# InverterSchematic.net
KiCad netlist of a schematic drawn in Altium Designer
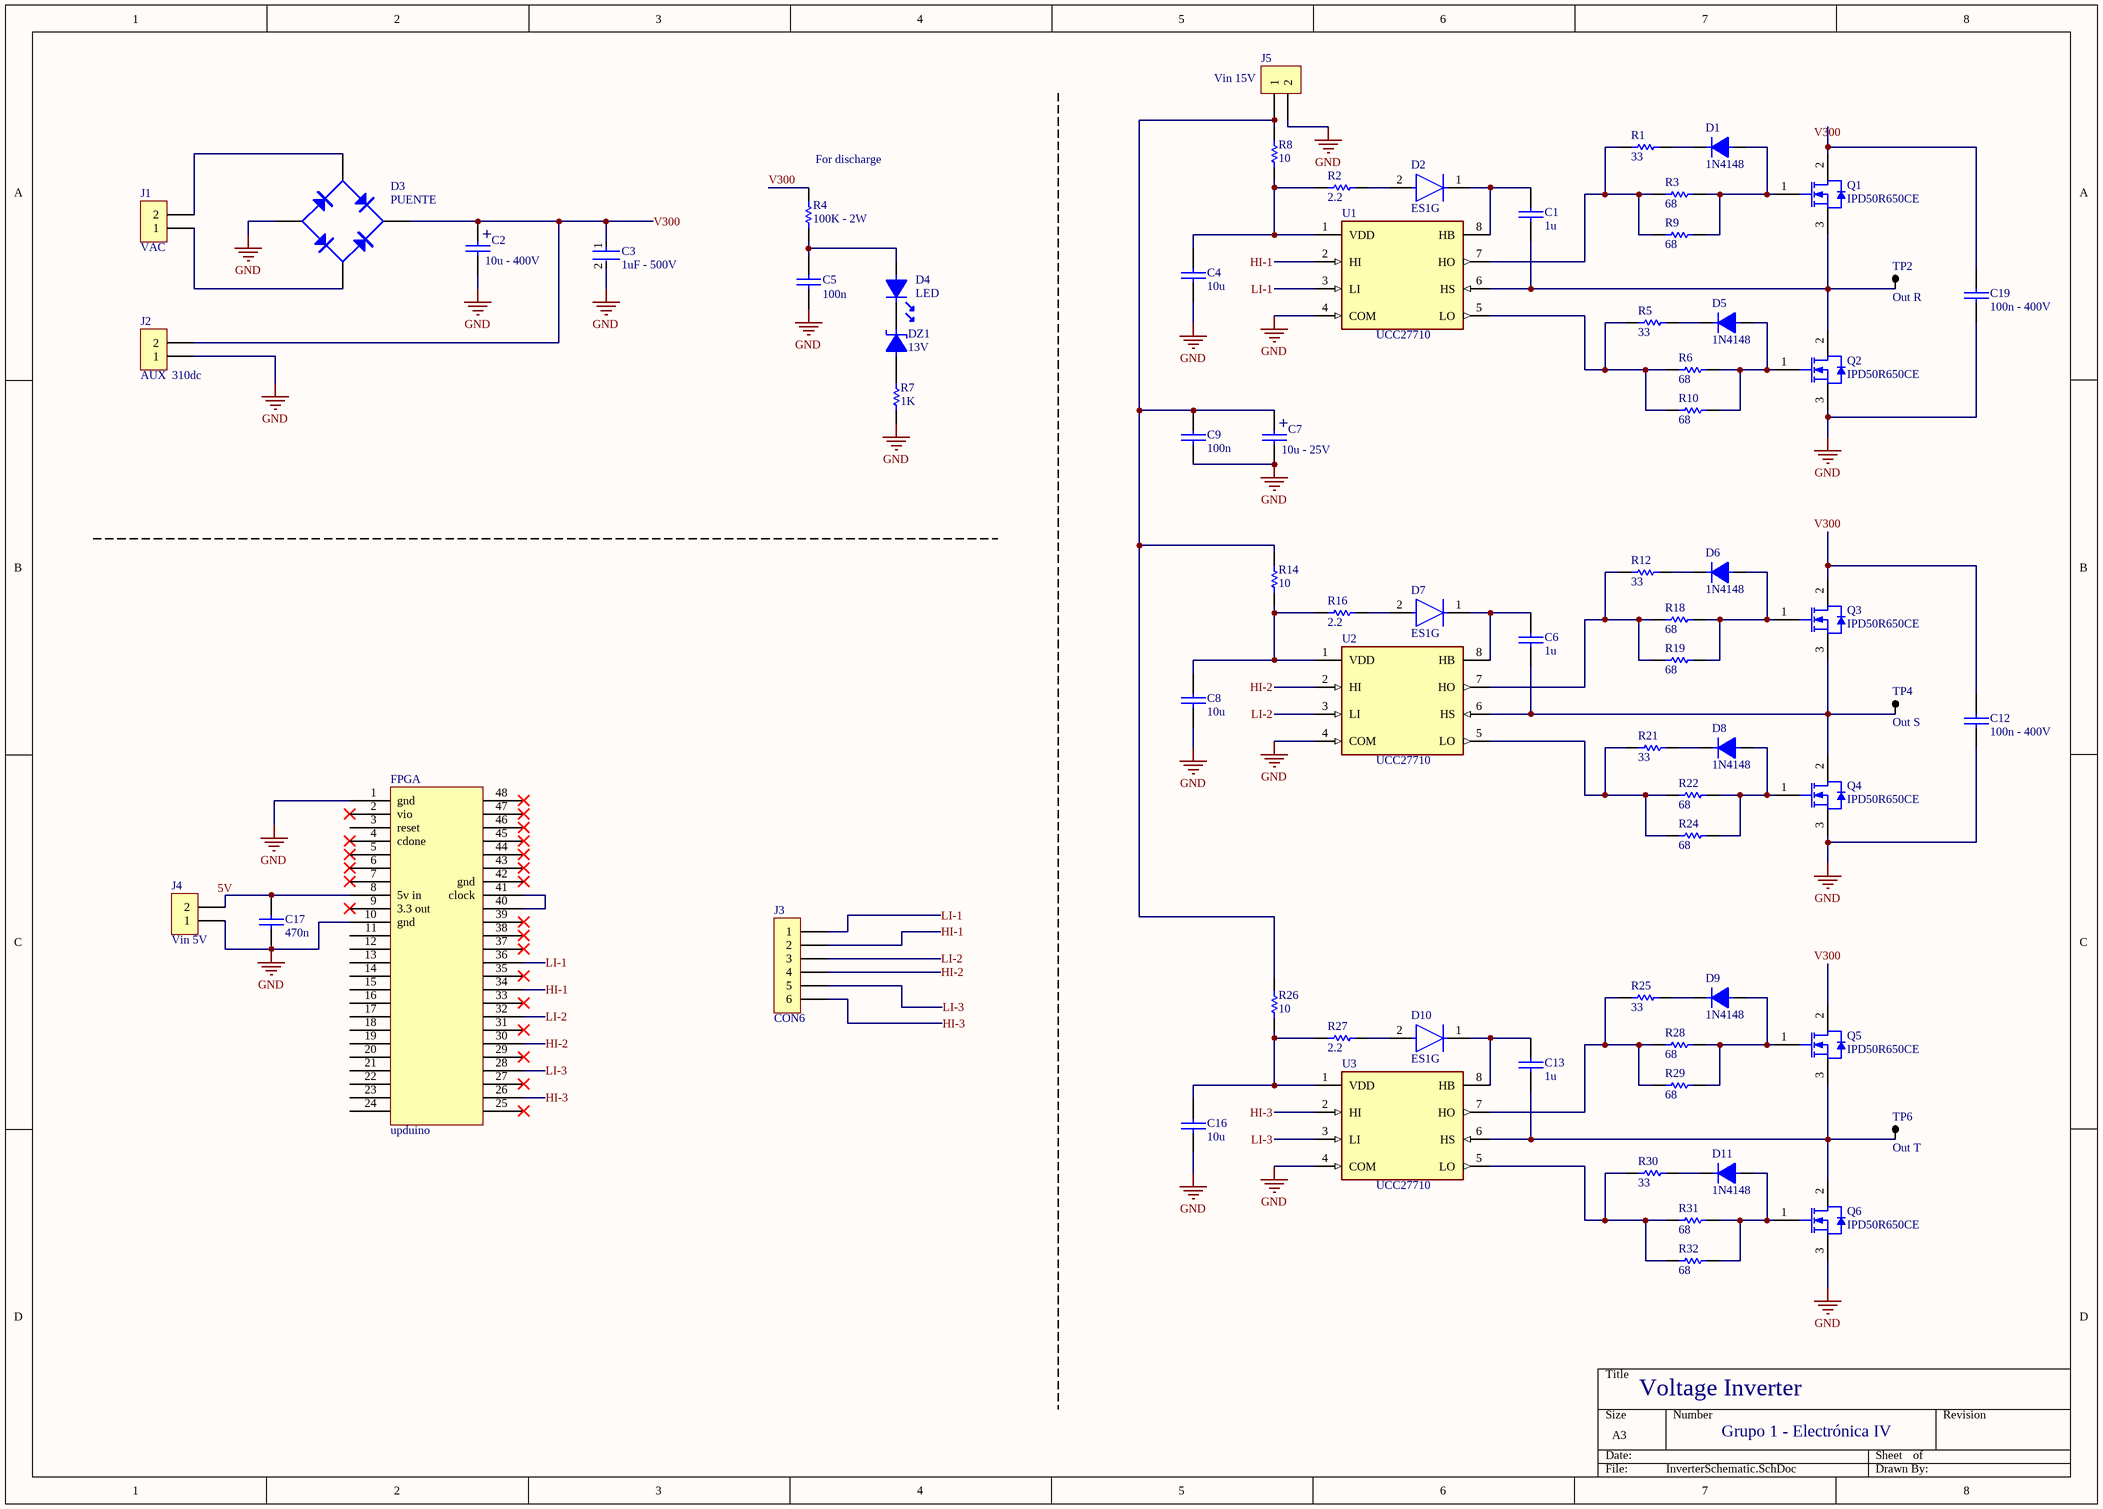
[diagram p0: InverterSchematic.SchDoc]

(export (version "E")
  (design (tool "Eeschema 10.0.6"))
  (components
    (comp (ref "C1") (value "1u") (footprint "0805") (libsource (lib "LIBEBAL") (part "CAP")))
    (comp (ref "C2")
      (value "10u - 400V")
      (footprint "CAP200RP2")
      (libsource (lib "LIBEBAL Tobi") (part "CAPPOL"))
    )
    (comp (ref "C3")
      (value "1uF - 500V")
      (footprint "FP-GRM55D-0_4-IPC_B")
      (description "Chip Multilayer Ceramic Capacitors for General Purpose, 2220, 1.0uF, X7R, 15%, 10%, 500V")
      (fields (field (name "VOLTAGE") "250V") (field (name "TOLERANCE") "10%"))
      (libsource (lib "Altium Content Vault") (part "b4654b650e69147ec39a6b967a45e02"))
    )
    (comp (ref "C4") (value "10u") (footprint "0805") (libsource (lib "LIBEBAL") (part "CAP")))
    (comp (ref "C5") (value "100n") (footprint "0805") (libsource (lib "LIBEBAL Tobi") (part "CAP")))
    (comp (ref "C6") (value "1u") (footprint "0805") (libsource (lib "LIBEBAL") (part "CAP")))
    (comp (ref "C7")
      (value "10u - 25V")
      (footprint "CAP100RP")
      (libsource (lib "LIBEBAL Tobi") (part "CAPPOL"))
    )
    (comp (ref "C8") (value "10u") (footprint "0805") (libsource (lib "LIBEBAL") (part "CAP")))
    (comp (ref "C9") (value "100n") (footprint "CAP200") (libsource (lib "LIBEBAL") (part "CAP")))
    (comp (ref "C12") (value "100n - 400V") (footprint "CAP200") (libsource (lib "LIBEBAL") (part "CAP")))
    (comp (ref "C13") (value "1u") (footprint "0805") (libsource (lib "LIBEBAL") (part "CAP")))
    (comp (ref "C16") (value "10u") (footprint "0805") (libsource (lib "LIBEBAL") (part "CAP")))
    (comp (ref "C17") (value "470n") (footprint "0805") (libsource (lib "LIBEBAL") (part "CAP")))
    (comp (ref "C19") (value "100n - 400V") (footprint "CAP200") (libsource (lib "LIBEBAL") (part "CAP")))
    (comp (ref "D1") (value "1N4148") (footprint "DO41") (libsource (lib "LIBEBAL") (part "DIODO")))
    (comp (ref "D2")
      (value "ES1G")
      (footprint "FP-403AE-MFG")
      (description "DIODE GEN PURP 400V 1A SMA")
      (fields
        (field (name "OCTOPART") "https://octopart.com/es1g-on+semiconductor-84324858")
        (field (name "MANUFACTURER") "ON Semiconductor")
      )
      (libsource (lib "Altium Content Vault") (part "d7152d700b627762746794eb795d46e"))
    )
    (comp (ref "D3")
      (value "PUENTE")
      (footprint "PUENTE - W10M")
      (libsource (lib "LIBEBAL Tobi") (part "PUENTE"))
    )
    (comp (ref "D4") (value "LED") (footprint "LED3") (libsource (lib "LIBEBAL Tobi") (part "LED")))
    (comp (ref "D5") (value "1N4148") (footprint "DO41") (libsource (lib "LIBEBAL") (part "DIODO")))
    (comp (ref "D6") (value "1N4148") (footprint "DO41") (libsource (lib "LIBEBAL") (part "DIODO")))
    (comp (ref "D7")
      (value "ES1G")
      (footprint "FP-403AE-MFG")
      (description "DIODE GEN PURP 400V 1A SMA")
      (fields
        (field (name "OCTOPART") "https://octopart.com/es1g-on+semiconductor-84324858")
        (field (name "MANUFACTURER") "ON Semiconductor")
      )
      (libsource (lib "Altium Content Vault") (part "d7152d700b627762746794eb795d46e"))
    )
    (comp (ref "D8") (value "1N4148") (footprint "DO41") (libsource (lib "LIBEBAL") (part "DIODO")))
    (comp (ref "D9") (value "1N4148") (footprint "DO41") (libsource (lib "LIBEBAL") (part "DIODO")))
    (comp (ref "D10")
      (value "ES1G")
      (footprint "FP-403AE-MFG")
      (description "DIODE GEN PURP 400V 1A SMA")
      (fields
        (field (name "OCTOPART") "https://octopart.com/es1g-on+semiconductor-84324858")
        (field (name "MANUFACTURER") "ON Semiconductor")
      )
      (libsource (lib "Altium Content Vault") (part "d7152d700b627762746794eb795d46e"))
    )
    (comp (ref "D11") (value "1N4148") (footprint "DO41") (libsource (lib "LIBEBAL") (part "DIODO")))
    (comp (ref "DZ1") (value "13V") (footprint "DO41") (libsource (lib "LIBEBAL Tobi") (part "DIODO ZENER")))
    (comp (ref "FPGA")
      (value "upduino")
      (footprint "FPGA")
      (description "upduino v3.0")
      (libsource (lib "InverterSchLib") (part "FPGA"))
    )
    (comp (ref "J1") (value "VAC") (footprint "BORNERA2") (libsource (lib "LIBEBAL Tobi") (part "BORNERA 2")))
    (comp (ref "J2")
      (value "AUX  310dc")
      (footprint "BORNERA2")
      (libsource (lib "LIBEBAL Tobi") (part "BORNERA 2"))
    )
    (comp (ref "J3") (value "CON6") (footprint "SIP6") (libsource (lib "LIBEBAL") (part "CON6")))
    (comp (ref "J4")
      (value "Vin 5V")
      (footprint "SIP2")
      (description "UPDuino Power Input")
      (libsource (lib "LIBEBAL Tobi") (part "CON2"))
    )
    (comp (ref "J5")
      (value "Vin 15V")
      (footprint "SIP2")
      (description "UPDuino Power Input")
      (libsource (lib "") (part "CON2_1"))
    )
    (comp (ref "Q1")
      (value "IPD50R650CE")
      (footprint "INF-PG-TO252-3-313_N")
      (fields (field (name "MANUFACTURER") "Infineon"))
      (libsource (lib "Altium Content Vault") (part "INF-NEMOS-GDS-3"))
    )
    (comp (ref "Q2")
      (value "IPD50R650CE")
      (footprint "INF-PG-TO252-3-313_N")
      (fields (field (name "MANUFACTURER") "Infineon"))
      (libsource (lib "Altium Content Vault") (part "INF-NEMOS-GDS-3"))
    )
    (comp (ref "Q3")
      (value "IPD50R650CE")
      (footprint "INF-PG-TO252-3-313_N")
      (fields (field (name "MANUFACTURER") "Infineon"))
      (libsource (lib "Altium Content Vault") (part "INF-NEMOS-GDS-3"))
    )
    (comp (ref "Q4")
      (value "IPD50R650CE")
      (footprint "INF-PG-TO252-3-313_N")
      (fields (field (name "MANUFACTURER") "Infineon"))
      (libsource (lib "Altium Content Vault") (part "INF-NEMOS-GDS-3"))
    )
    (comp (ref "Q5")
      (value "IPD50R650CE")
      (footprint "INF-PG-TO252-3-313_N")
      (fields (field (name "MANUFACTURER") "Infineon"))
      (libsource (lib "Altium Content Vault") (part "INF-NEMOS-GDS-3"))
    )
    (comp (ref "Q6")
      (value "IPD50R650CE")
      (footprint "INF-PG-TO252-3-313_N")
      (fields (field (name "MANUFACTURER") "Infineon"))
      (libsource (lib "Altium Content Vault") (part "INF-NEMOS-GDS-3"))
    )
    (comp (ref "R1")
      (value "33")
      (footprint "0805")
      (description "33?")
      (libsource (lib "LIBEBAL") (part "RES"))
    )
    (comp (ref "R2") (value "2.2") (footprint "RES300") (libsource (lib "LIBEBAL") (part "RES")))
    (comp (ref "R3") (value "68") (footprint "0805") (libsource (lib "LIBEBAL") (part "RES")))
    (comp (ref "R4") (value "100K - 2W") (footprint "RES300") (libsource (lib "LIBEBAL Tobi") (part "RES")))
    (comp (ref "R5") (value "33") (footprint "0805") (libsource (lib "LIBEBAL") (part "RES")))
    (comp (ref "R6") (value "68") (footprint "0805") (libsource (lib "LIBEBAL") (part "RES")))
    (comp (ref "R7") (value "1K") (footprint "0805") (libsource (lib "LIBEBAL") (part "RES")))
    (comp (ref "R8") (value "10") (footprint "RES300") (libsource (lib "LIBEBAL") (part "RES")))
    (comp (ref "R9") (value "68") (footprint "0805") (libsource (lib "LIBEBAL") (part "RES")))
    (comp (ref "R10") (value "68") (footprint "0805") (libsource (lib "LIBEBAL") (part "RES")))
    (comp (ref "R12")
      (value "33")
      (footprint "0805")
      (description "33?")
      (libsource (lib "LIBEBAL") (part "RES"))
    )
    (comp (ref "R14") (value "10") (footprint "RES300") (libsource (lib "LIBEBAL") (part "RES")))
    (comp (ref "R16") (value "2.2") (footprint "RES300") (libsource (lib "LIBEBAL") (part "RES")))
    (comp (ref "R18") (value "68") (footprint "0805") (libsource (lib "LIBEBAL") (part "RES")))
    (comp (ref "R19") (value "68") (footprint "0805") (libsource (lib "LIBEBAL") (part "RES")))
    (comp (ref "R21") (value "33") (footprint "0805") (libsource (lib "LIBEBAL") (part "RES")))
    (comp (ref "R22") (value "68") (footprint "0805") (libsource (lib "LIBEBAL") (part "RES")))
    (comp (ref "R24") (value "68") (footprint "0805") (libsource (lib "LIBEBAL") (part "RES")))
    (comp (ref "R25")
      (value "33")
      (footprint "0805")
      (description "33?")
      (libsource (lib "LIBEBAL") (part "RES"))
    )
    (comp (ref "R26") (value "10") (footprint "RES300") (libsource (lib "LIBEBAL") (part "RES")))
    (comp (ref "R27") (value "2.2") (footprint "RES300") (libsource (lib "LIBEBAL") (part "RES")))
    (comp (ref "R28") (value "68") (footprint "0805") (libsource (lib "LIBEBAL") (part "RES")))
    (comp (ref "R29") (value "68") (footprint "0805") (libsource (lib "LIBEBAL") (part "RES")))
    (comp (ref "R30") (value "33") (footprint "0805") (libsource (lib "LIBEBAL") (part "RES")))
    (comp (ref "R31") (value "68") (footprint "0805") (libsource (lib "LIBEBAL") (part "RES")))
    (comp (ref "R32") (value "68") (footprint "0805") (libsource (lib "LIBEBAL") (part "RES")))
    (comp (ref "TP2") (value "Out R") (footprint "TPTH") (libsource (lib "LIBEBAL") (part "TP")))
    (comp (ref "TP4") (value "Out S") (footprint "TPTH") (libsource (lib "LIBEBAL") (part "TP")))
    (comp (ref "TP6") (value "Out T") (footprint "TPTH") (libsource (lib "LIBEBAL") (part "TP")))
    (comp (ref "U1")
      (value "UCC27710")
      (footprint "FP-PG-DSO-8-IPC_C")
      (description "GATE DRVR HI/LOW SIDE 8SOIC")
      (libsource (lib "Altium Content Vault") (part "f43bf47bf2763d79e2fe7860ecc000c"))
    )
    (comp (ref "U2")
      (value "UCC27710")
      (footprint "FP-PG-DSO-8-IPC_C")
      (description "GATE DRVR HI/LOW SIDE 8SOIC")
      (libsource (lib "Altium Content Vault") (part "f43bf47bf2763d79e2fe7860ecc000c"))
    )
    (comp (ref "U3")
      (value "UCC27710")
      (footprint "FP-PG-DSO-8-IPC_C")
      (description "GATE DRVR HI/LOW SIDE 8SOIC")
      (libsource (lib "Altium Content Vault") (part "f43bf47bf2763d79e2fe7860ecc000c"))
    )
  )
  (nets
    (net (code "1") (name "/5V") (class "Default")
      (node (ref "C17") (pin "1") (pinfunction "1_1") (pintype "passive"))
      (node (ref "FPGA") (pin "8") (pinfunction "5v_in_8") (pintype "passive"))
      (node (ref "J4") (pin "2") (pinfunction "2_2") (pintype "passive"))
    )
    (net (code "2") (name "/HI-1") (class "Default")
      (node (ref "FPGA") (pin "34") (pintype "passive"))
      (node (ref "J3") (pin "2") (pinfunction "2_2") (pintype "passive"))
      (node (ref "U1") (pin "2") (pinfunction "HI_2") (pintype "input"))
    )
    (net (code "3") (name "/HI-2") (class "Default")
      (node (ref "FPGA") (pin "30") (pintype "passive"))
      (node (ref "J3") (pin "4") (pinfunction "4_4") (pintype "passive"))
      (node (ref "U2") (pin "2") (pinfunction "HI_2") (pintype "input"))
    )
    (net (code "4") (name "/HI-3") (class "Default")
      (node (ref "FPGA") (pin "26") (pintype "passive"))
      (node (ref "J3") (pin "6") (pinfunction "6_6") (pintype "passive"))
      (node (ref "U3") (pin "2") (pinfunction "HI_2") (pintype "input"))
    )
    (net (code "5") (name "/LI-1") (class "Default")
      (node (ref "FPGA") (pin "36") (pintype "passive"))
      (node (ref "J3") (pin "1") (pinfunction "1_1") (pintype "passive"))
      (node (ref "U1") (pin "3") (pinfunction "LI_3") (pintype "input"))
    )
    (net (code "6") (name "/LI-2") (class "Default")
      (node (ref "FPGA") (pin "32") (pintype "passive"))
      (node (ref "J3") (pin "3") (pinfunction "3_3") (pintype "passive"))
      (node (ref "U2") (pin "3") (pinfunction "LI_3") (pintype "input"))
    )
    (net (code "7") (name "/LI-3") (class "Default")
      (node (ref "FPGA") (pin "28") (pintype "passive"))
      (node (ref "J3") (pin "5") (pinfunction "5_5") (pintype "passive"))
      (node (ref "U3") (pin "3") (pinfunction "LI_3") (pintype "input"))
    )
    (net (code "8") (name "/V300") (class "Default")
      (node (ref "C12") (pin "1") (pinfunction "1_1") (pintype "passive"))
      (node (ref "C19") (pin "1") (pinfunction "1_1") (pintype "passive"))
      (node (ref "C2") (pin "1") (pinfunction "1_1") (pintype "passive"))
      (node (ref "C3") (pin "1") (pinfunction "1_1") (pintype "passive"))
      (node (ref "D3") (pin "1") (pinfunction "V+_1") (pintype "passive"))
      (node (ref "J2") (pin "2") (pinfunction "2_2") (pintype "passive"))
      (node (ref "Q1") (pin "2") (pinfunction "DRAIN_2") (pintype "passive"))
      (node (ref "Q3") (pin "2") (pinfunction "DRAIN_2") (pintype "passive"))
      (node (ref "Q5") (pin "2") (pinfunction "DRAIN_2") (pintype "passive"))
      (node (ref "R4") (pin "2") (pinfunction "2_2") (pintype "passive"))
    )
    (net (code "9") (name "GND") (class "Default")
      (node (ref "C12") (pin "2") (pinfunction "2_2") (pintype "passive"))
      (node (ref "C16") (pin "2") (pinfunction "2_2") (pintype "passive"))
      (node (ref "C17") (pin "2") (pinfunction "2_2") (pintype "passive"))
      (node (ref "C19") (pin "2") (pinfunction "2_2") (pintype "passive"))
      (node (ref "C2") (pin "2") (pinfunction "2_2") (pintype "passive"))
      (node (ref "C3") (pin "2") (pinfunction "2_2") (pintype "passive"))
      (node (ref "C4") (pin "2") (pinfunction "2_2") (pintype "passive"))
      (node (ref "C5") (pin "1") (pinfunction "1_1") (pintype "passive"))
      (node (ref "C7") (pin "2") (pinfunction "2_2") (pintype "passive"))
      (node (ref "C8") (pin "2") (pinfunction "2_2") (pintype "passive"))
      (node (ref "C9") (pin "2") (pinfunction "2_2") (pintype "passive"))
      (node (ref "D3") (pin "3") (pinfunction "V-_3") (pintype "passive"))
      (node (ref "FPGA") (pin "1") (pinfunction "gnd_1") (pintype "passive"))
      (node (ref "FPGA") (pin "10") (pinfunction "gnd_10") (pintype "passive"))
      (node (ref "J2") (pin "1") (pinfunction "1_1") (pintype "passive"))
      (node (ref "J4") (pin "1") (pinfunction "1_1") (pintype "passive"))
      (node (ref "J5") (pin "2") (pinfunction "2_2") (pintype "passive"))
      (node (ref "Q2") (pin "3") (pinfunction "SOURCE_3") (pintype "passive"))
      (node (ref "Q4") (pin "3") (pinfunction "SOURCE_3") (pintype "passive"))
      (node (ref "Q6") (pin "3") (pinfunction "SOURCE_3") (pintype "passive"))
      (node (ref "R7") (pin "2") (pinfunction "2_2") (pintype "passive"))
      (node (ref "U1") (pin "4") (pinfunction "COM_4") (pintype "input"))
      (node (ref "U2") (pin "4") (pinfunction "COM_4") (pintype "input"))
      (node (ref "U3") (pin "4") (pinfunction "COM_4") (pintype "input"))
    )
    (net (code "10") (name "Net-(C5-Pad2)") (class "Default")
      (node (ref "C5") (pin "2") (pinfunction "2_2") (pintype "passive"))
      (node (ref "D4") (pin "1") (pinfunction "1_1") (pintype "passive"))
      (node (ref "R4") (pin "1") (pinfunction "1_1") (pintype "passive"))
    )
    (net (code "11") (name "Net-(C7-Pad1)") (class "Default")
      (node (ref "C7") (pin "1") (pinfunction "1_1") (pintype "passive"))
      (node (ref "C9") (pin "1") (pinfunction "1_1") (pintype "passive"))
      (node (ref "J5") (pin "1") (pinfunction "1_1") (pintype "passive"))
      (node (ref "R14") (pin "2") (pinfunction "2_2") (pintype "passive"))
      (node (ref "R26") (pin "2") (pinfunction "2_2") (pintype "passive"))
      (node (ref "R8") (pin "2") (pinfunction "2_2") (pintype "passive"))
    )
    (net (code "12") (name "Net-(D1-Pad2)") (class "Default")
      (node (ref "D1") (pin "2") (pinfunction "2_2") (pintype "passive"))
      (node (ref "R1") (pin "2") (pinfunction "2_2") (pintype "passive"))
    )
    (net (code "13") (name "Net-(D2-A)") (class "Default")
      (node (ref "D2") (pin "2") (pinfunction "A_2") (pintype "passive"))
      (node (ref "R2") (pin "2") (pinfunction "2_2") (pintype "passive"))
    )
    (net (code "14") (name "Net-(D2-C)") (class "Default")
      (node (ref "C1") (pin "1") (pinfunction "1_1") (pintype "passive"))
      (node (ref "D2") (pin "1") (pinfunction "C_1") (pintype "passive"))
      (node (ref "U1") (pin "8") (pinfunction "HB_8") (pintype "passive"))
    )
    (net (code "15") (name "Net-(D3-AC-Pad2)") (class "Default")
      (node (ref "D3") (pin "2") (pinfunction "AC_2") (pintype "passive"))
      (node (ref "J1") (pin "2") (pinfunction "2_2") (pintype "passive"))
    )
    (net (code "16") (name "Net-(D3-AC-Pad4)") (class "Default")
      (node (ref "D3") (pin "4") (pinfunction "AC_4") (pintype "passive"))
      (node (ref "J1") (pin "1") (pinfunction "1_1") (pintype "passive"))
    )
    (net (code "17") (name "Net-(D4-Pad2)") (class "Default")
      (node (ref "D4") (pin "2") (pinfunction "2_2") (pintype "passive"))
      (node (ref "DZ1") (pin "2") (pinfunction "2_2") (pintype "passive"))
    )
    (net (code "18") (name "Net-(D5-Pad2)") (class "Default")
      (node (ref "D5") (pin "2") (pinfunction "2_2") (pintype "passive"))
      (node (ref "R5") (pin "2") (pinfunction "2_2") (pintype "passive"))
    )
    (net (code "19") (name "Net-(D6-Pad2)") (class "Default")
      (node (ref "D6") (pin "2") (pinfunction "2_2") (pintype "passive"))
      (node (ref "R12") (pin "2") (pinfunction "2_2") (pintype "passive"))
    )
    (net (code "20") (name "Net-(D7-A)") (class "Default")
      (node (ref "D7") (pin "2") (pinfunction "A_2") (pintype "passive"))
      (node (ref "R16") (pin "2") (pinfunction "2_2") (pintype "passive"))
    )
    (net (code "21") (name "Net-(D7-C)") (class "Default")
      (node (ref "C6") (pin "1") (pinfunction "1_1") (pintype "passive"))
      (node (ref "D7") (pin "1") (pinfunction "C_1") (pintype "passive"))
      (node (ref "U2") (pin "8") (pinfunction "HB_8") (pintype "passive"))
    )
    (net (code "22") (name "Net-(D8-Pad2)") (class "Default")
      (node (ref "D8") (pin "2") (pinfunction "2_2") (pintype "passive"))
      (node (ref "R21") (pin "2") (pinfunction "2_2") (pintype "passive"))
    )
    (net (code "23") (name "Net-(D9-Pad2)") (class "Default")
      (node (ref "D9") (pin "2") (pinfunction "2_2") (pintype "passive"))
      (node (ref "R25") (pin "2") (pinfunction "2_2") (pintype "passive"))
    )
    (net (code "24") (name "Net-(D10-A)") (class "Default")
      (node (ref "D10") (pin "2") (pinfunction "A_2") (pintype "passive"))
      (node (ref "R27") (pin "2") (pinfunction "2_2") (pintype "passive"))
    )
    (net (code "25") (name "Net-(D10-C)") (class "Default")
      (node (ref "C13") (pin "1") (pinfunction "1_1") (pintype "passive"))
      (node (ref "D10") (pin "1") (pinfunction "C_1") (pintype "passive"))
      (node (ref "U3") (pin "8") (pinfunction "HB_8") (pintype "passive"))
    )
    (net (code "26") (name "Net-(D11-Pad2)") (class "Default")
      (node (ref "D11") (pin "2") (pinfunction "2_2") (pintype "passive"))
      (node (ref "R30") (pin "2") (pinfunction "2_2") (pintype "passive"))
    )
    (net (code "27") (name "Net-(DZ1-Pad1)") (class "Default")
      (node (ref "DZ1") (pin "1") (pinfunction "1_1") (pintype "passive"))
      (node (ref "R7") (pin "1") (pinfunction "1_1") (pintype "passive"))
    )
    (net (code "28") (name "Net-(FPGA-clock)") (class "Default")
      (node (ref "FPGA") (pin "40") (pintype "passive"))
      (node (ref "FPGA") (pin "41") (pinfunction "clock_41") (pintype "passive"))
    )
    (net (code "29") (name "Net-(Q1-GATE)") (class "Default")
      (node (ref "D1") (pin "1") (pinfunction "1_1") (pintype "passive"))
      (node (ref "Q1") (pin "1") (pinfunction "GATE_1") (pintype "passive"))
      (node (ref "R3") (pin "2") (pinfunction "2_2") (pintype "passive"))
      (node (ref "R9") (pin "2") (pinfunction "2_2") (pintype "passive"))
    )
    (net (code "30") (name "Net-(Q1-SOURCE)") (class "Default")
      (node (ref "C1") (pin "2") (pinfunction "2_2") (pintype "passive"))
      (node (ref "Q1") (pin "3") (pinfunction "SOURCE_3") (pintype "passive"))
      (node (ref "Q2") (pin "2") (pinfunction "DRAIN_2") (pintype "passive"))
      (node (ref "TP2") (pin "1") (pinfunction "1_1") (pintype "passive"))
      (node (ref "U1") (pin "6") (pinfunction "HS_6") (pintype "input"))
    )
    (net (code "31") (name "Net-(Q2-GATE)") (class "Default")
      (node (ref "D5") (pin "1") (pinfunction "1_1") (pintype "passive"))
      (node (ref "Q2") (pin "1") (pinfunction "GATE_1") (pintype "passive"))
      (node (ref "R10") (pin "2") (pinfunction "2_2") (pintype "passive"))
      (node (ref "R6") (pin "2") (pinfunction "2_2") (pintype "passive"))
    )
    (net (code "32") (name "Net-(Q3-GATE)") (class "Default")
      (node (ref "D6") (pin "1") (pinfunction "1_1") (pintype "passive"))
      (node (ref "Q3") (pin "1") (pinfunction "GATE_1") (pintype "passive"))
      (node (ref "R18") (pin "2") (pinfunction "2_2") (pintype "passive"))
      (node (ref "R19") (pin "2") (pinfunction "2_2") (pintype "passive"))
    )
    (net (code "33") (name "Net-(Q3-SOURCE)") (class "Default")
      (node (ref "C6") (pin "2") (pinfunction "2_2") (pintype "passive"))
      (node (ref "Q3") (pin "3") (pinfunction "SOURCE_3") (pintype "passive"))
      (node (ref "Q4") (pin "2") (pinfunction "DRAIN_2") (pintype "passive"))
      (node (ref "TP4") (pin "1") (pinfunction "1_1") (pintype "passive"))
      (node (ref "U2") (pin "6") (pinfunction "HS_6") (pintype "input"))
    )
    (net (code "34") (name "Net-(Q4-GATE)") (class "Default")
      (node (ref "D8") (pin "1") (pinfunction "1_1") (pintype "passive"))
      (node (ref "Q4") (pin "1") (pinfunction "GATE_1") (pintype "passive"))
      (node (ref "R22") (pin "2") (pinfunction "2_2") (pintype "passive"))
      (node (ref "R24") (pin "2") (pinfunction "2_2") (pintype "passive"))
    )
    (net (code "35") (name "Net-(Q5-GATE)") (class "Default")
      (node (ref "D9") (pin "1") (pinfunction "1_1") (pintype "passive"))
      (node (ref "Q5") (pin "1") (pinfunction "GATE_1") (pintype "passive"))
      (node (ref "R28") (pin "2") (pinfunction "2_2") (pintype "passive"))
      (node (ref "R29") (pin "2") (pinfunction "2_2") (pintype "passive"))
    )
    (net (code "36") (name "Net-(Q5-SOURCE)") (class "Default")
      (node (ref "C13") (pin "2") (pinfunction "2_2") (pintype "passive"))
      (node (ref "Q5") (pin "3") (pinfunction "SOURCE_3") (pintype "passive"))
      (node (ref "Q6") (pin "2") (pinfunction "DRAIN_2") (pintype "passive"))
      (node (ref "TP6") (pin "1") (pinfunction "1_1") (pintype "passive"))
      (node (ref "U3") (pin "6") (pinfunction "HS_6") (pintype "input"))
    )
    (net (code "37") (name "Net-(Q6-GATE)") (class "Default")
      (node (ref "D11") (pin "1") (pinfunction "1_1") (pintype "passive"))
      (node (ref "Q6") (pin "1") (pinfunction "GATE_1") (pintype "passive"))
      (node (ref "R31") (pin "2") (pinfunction "2_2") (pintype "passive"))
      (node (ref "R32") (pin "2") (pinfunction "2_2") (pintype "passive"))
    )
    (net (code "38") (name "Net-(U1-HO)") (class "Default")
      (node (ref "R1") (pin "1") (pinfunction "1_1") (pintype "passive"))
      (node (ref "R3") (pin "1") (pinfunction "1_1") (pintype "passive"))
      (node (ref "R9") (pin "1") (pinfunction "1_1") (pintype "passive"))
      (node (ref "U1") (pin "7") (pinfunction "HO_7") (pintype "output"))
    )
    (net (code "39") (name "Net-(U1-LO)") (class "Default")
      (node (ref "R10") (pin "1") (pinfunction "1_1") (pintype "passive"))
      (node (ref "R5") (pin "1") (pinfunction "1_1") (pintype "passive"))
      (node (ref "R6") (pin "1") (pinfunction "1_1") (pintype "passive"))
      (node (ref "U1") (pin "5") (pinfunction "LO_5") (pintype "output"))
    )
    (net (code "40") (name "Net-(U1-VDD)") (class "Default")
      (node (ref "C4") (pin "1") (pinfunction "1_1") (pintype "passive"))
      (node (ref "R2") (pin "1") (pinfunction "1_1") (pintype "passive"))
      (node (ref "R8") (pin "1") (pinfunction "1_1") (pintype "passive"))
      (node (ref "U1") (pin "1") (pinfunction "VDD_1") (pintype "power_in"))
    )
    (net (code "41") (name "Net-(U2-HO)") (class "Default")
      (node (ref "R12") (pin "1") (pinfunction "1_1") (pintype "passive"))
      (node (ref "R18") (pin "1") (pinfunction "1_1") (pintype "passive"))
      (node (ref "R19") (pin "1") (pinfunction "1_1") (pintype "passive"))
      (node (ref "U2") (pin "7") (pinfunction "HO_7") (pintype "output"))
    )
    (net (code "42") (name "Net-(U2-LO)") (class "Default")
      (node (ref "R21") (pin "1") (pinfunction "1_1") (pintype "passive"))
      (node (ref "R22") (pin "1") (pinfunction "1_1") (pintype "passive"))
      (node (ref "R24") (pin "1") (pinfunction "1_1") (pintype "passive"))
      (node (ref "U2") (pin "5") (pinfunction "LO_5") (pintype "output"))
    )
    (net (code "43") (name "Net-(U2-VDD)") (class "Default")
      (node (ref "C8") (pin "1") (pinfunction "1_1") (pintype "passive"))
      (node (ref "R14") (pin "1") (pinfunction "1_1") (pintype "passive"))
      (node (ref "R16") (pin "1") (pinfunction "1_1") (pintype "passive"))
      (node (ref "U2") (pin "1") (pinfunction "VDD_1") (pintype "power_in"))
    )
    (net (code "44") (name "Net-(U3-HO)") (class "Default")
      (node (ref "R25") (pin "1") (pinfunction "1_1") (pintype "passive"))
      (node (ref "R28") (pin "1") (pinfunction "1_1") (pintype "passive"))
      (node (ref "R29") (pin "1") (pinfunction "1_1") (pintype "passive"))
      (node (ref "U3") (pin "7") (pinfunction "HO_7") (pintype "output"))
    )
    (net (code "45") (name "Net-(U3-LO)") (class "Default")
      (node (ref "R30") (pin "1") (pinfunction "1_1") (pintype "passive"))
      (node (ref "R31") (pin "1") (pinfunction "1_1") (pintype "passive"))
      (node (ref "R32") (pin "1") (pinfunction "1_1") (pintype "passive"))
      (node (ref "U3") (pin "5") (pinfunction "LO_5") (pintype "output"))
    )
    (net (code "46") (name "Net-(U3-VDD)") (class "Default")
      (node (ref "C16") (pin "1") (pinfunction "1_1") (pintype "passive"))
      (node (ref "R26") (pin "1") (pinfunction "1_1") (pintype "passive"))
      (node (ref "R27") (pin "1") (pinfunction "1_1") (pintype "passive"))
      (node (ref "U3") (pin "1") (pinfunction "VDD_1") (pintype "power_in"))
    )
    (net (code "47") (name "unconnected-(FPGA-3.3_out-Pad9)") (class "Default")
      (node (ref "FPGA") (pin "9") (pinfunction "3.3_out_9") (pintype "passive+no_connect"))
    )
    (net (code "48") (name "unconnected-(FPGA-Pad5)") (class "Default")
      (node (ref "FPGA") (pin "5") (pintype "passive+no_connect"))
    )
    (net (code "49") (name "unconnected-(FPGA-Pad6)") (class "Default")
      (node (ref "FPGA") (pin "6") (pintype "passive+no_connect"))
    )
    (net (code "50") (name "unconnected-(FPGA-Pad7)") (class "Default")
      (node (ref "FPGA") (pin "7") (pintype "passive+no_connect"))
    )
    (net (code "51") (name "unconnected-(FPGA-Pad11)") (class "Default")
      (node (ref "FPGA") (pin "11") (pintype "passive"))
    )
    (net (code "52") (name "unconnected-(FPGA-Pad12)") (class "Default")
      (node (ref "FPGA") (pin "12") (pintype "passive"))
    )
    (net (code "53") (name "unconnected-(FPGA-Pad13)") (class "Default")
      (node (ref "FPGA") (pin "13") (pintype "passive"))
    )
    (net (code "54") (name "unconnected-(FPGA-Pad14)") (class "Default")
      (node (ref "FPGA") (pin "14") (pintype "passive"))
    )
    (net (code "55") (name "unconnected-(FPGA-Pad15)") (class "Default")
      (node (ref "FPGA") (pin "15") (pintype "passive"))
    )
    (net (code "56") (name "unconnected-(FPGA-Pad16)") (class "Default")
      (node (ref "FPGA") (pin "16") (pintype "passive"))
    )
    (net (code "57") (name "unconnected-(FPGA-Pad17)") (class "Default")
      (node (ref "FPGA") (pin "17") (pintype "passive"))
    )
    (net (code "58") (name "unconnected-(FPGA-Pad18)") (class "Default")
      (node (ref "FPGA") (pin "18") (pintype "passive"))
    )
    (net (code "59") (name "unconnected-(FPGA-Pad19)") (class "Default")
      (node (ref "FPGA") (pin "19") (pintype "passive"))
    )
    (net (code "60") (name "unconnected-(FPGA-Pad20)") (class "Default")
      (node (ref "FPGA") (pin "20") (pintype "passive"))
    )
    (net (code "61") (name "unconnected-(FPGA-Pad21)") (class "Default")
      (node (ref "FPGA") (pin "21") (pintype "passive"))
    )
    (net (code "62") (name "unconnected-(FPGA-Pad22)") (class "Default")
      (node (ref "FPGA") (pin "22") (pintype "passive"))
    )
    (net (code "63") (name "unconnected-(FPGA-Pad23)") (class "Default")
      (node (ref "FPGA") (pin "23") (pintype "passive"))
    )
    (net (code "64") (name "unconnected-(FPGA-Pad24)") (class "Default")
      (node (ref "FPGA") (pin "24") (pintype "passive"))
    )
    (net (code "65") (name "unconnected-(FPGA-Pad25)") (class "Default")
      (node (ref "FPGA") (pin "25") (pintype "passive+no_connect"))
    )
    (net (code "66") (name "unconnected-(FPGA-Pad27)") (class "Default")
      (node (ref "FPGA") (pin "27") (pintype "passive+no_connect"))
    )
    (net (code "67") (name "unconnected-(FPGA-Pad29)") (class "Default")
      (node (ref "FPGA") (pin "29") (pintype "passive+no_connect"))
    )
    (net (code "68") (name "unconnected-(FPGA-Pad31)") (class "Default")
      (node (ref "FPGA") (pin "31") (pintype "passive+no_connect"))
    )
    (net (code "69") (name "unconnected-(FPGA-Pad33)") (class "Default")
      (node (ref "FPGA") (pin "33") (pintype "passive+no_connect"))
    )
    (net (code "70") (name "unconnected-(FPGA-Pad35)") (class "Default")
      (node (ref "FPGA") (pin "35") (pintype "passive+no_connect"))
    )
    (net (code "71") (name "unconnected-(FPGA-Pad37)") (class "Default")
      (node (ref "FPGA") (pin "37") (pintype "passive+no_connect"))
    )
    (net (code "72") (name "unconnected-(FPGA-Pad38)") (class "Default")
      (node (ref "FPGA") (pin "38") (pintype "passive+no_connect"))
    )
    (net (code "73") (name "unconnected-(FPGA-Pad39)") (class "Default")
      (node (ref "FPGA") (pin "39") (pintype "passive+no_connect"))
    )
    (net (code "74") (name "unconnected-(FPGA-Pad43)") (class "Default")
      (node (ref "FPGA") (pin "43") (pintype "passive+no_connect"))
    )
    (net (code "75") (name "unconnected-(FPGA-Pad44)") (class "Default")
      (node (ref "FPGA") (pin "44") (pintype "passive+no_connect"))
    )
    (net (code "76") (name "unconnected-(FPGA-Pad45)") (class "Default")
      (node (ref "FPGA") (pin "45") (pintype "passive+no_connect"))
    )
    (net (code "77") (name "unconnected-(FPGA-Pad46)") (class "Default")
      (node (ref "FPGA") (pin "46") (pintype "passive+no_connect"))
    )
    (net (code "78") (name "unconnected-(FPGA-Pad47)") (class "Default")
      (node (ref "FPGA") (pin "47") (pintype "passive+no_connect"))
    )
    (net (code "79") (name "unconnected-(FPGA-Pad48)") (class "Default")
      (node (ref "FPGA") (pin "48") (pintype "passive+no_connect"))
    )
    (net (code "80") (name "unconnected-(FPGA-cdone-Pad4)") (class "Default")
      (node (ref "FPGA") (pin "4") (pinfunction "cdone_4") (pintype "passive+no_connect"))
    )
    (net (code "81") (name "unconnected-(FPGA-gnd-Pad42)") (class "Default")
      (node (ref "FPGA") (pin "42") (pinfunction "gnd_42") (pintype "passive+no_connect"))
    )
    (net (code "82") (name "unconnected-(FPGA-reset-Pad3)") (class "Default")
      (node (ref "FPGA") (pin "3") (pinfunction "reset_3") (pintype "passive"))
    )
    (net (code "83") (name "unconnected-(FPGA-vio-Pad2)") (class "Default")
      (node (ref "FPGA") (pin "2") (pinfunction "vio_2") (pintype "passive+no_connect"))
    )
  )
)
